# SCH_elliotcard_2024-12-29.net
KiCad netlist of a schematic drawn in EasyEDA
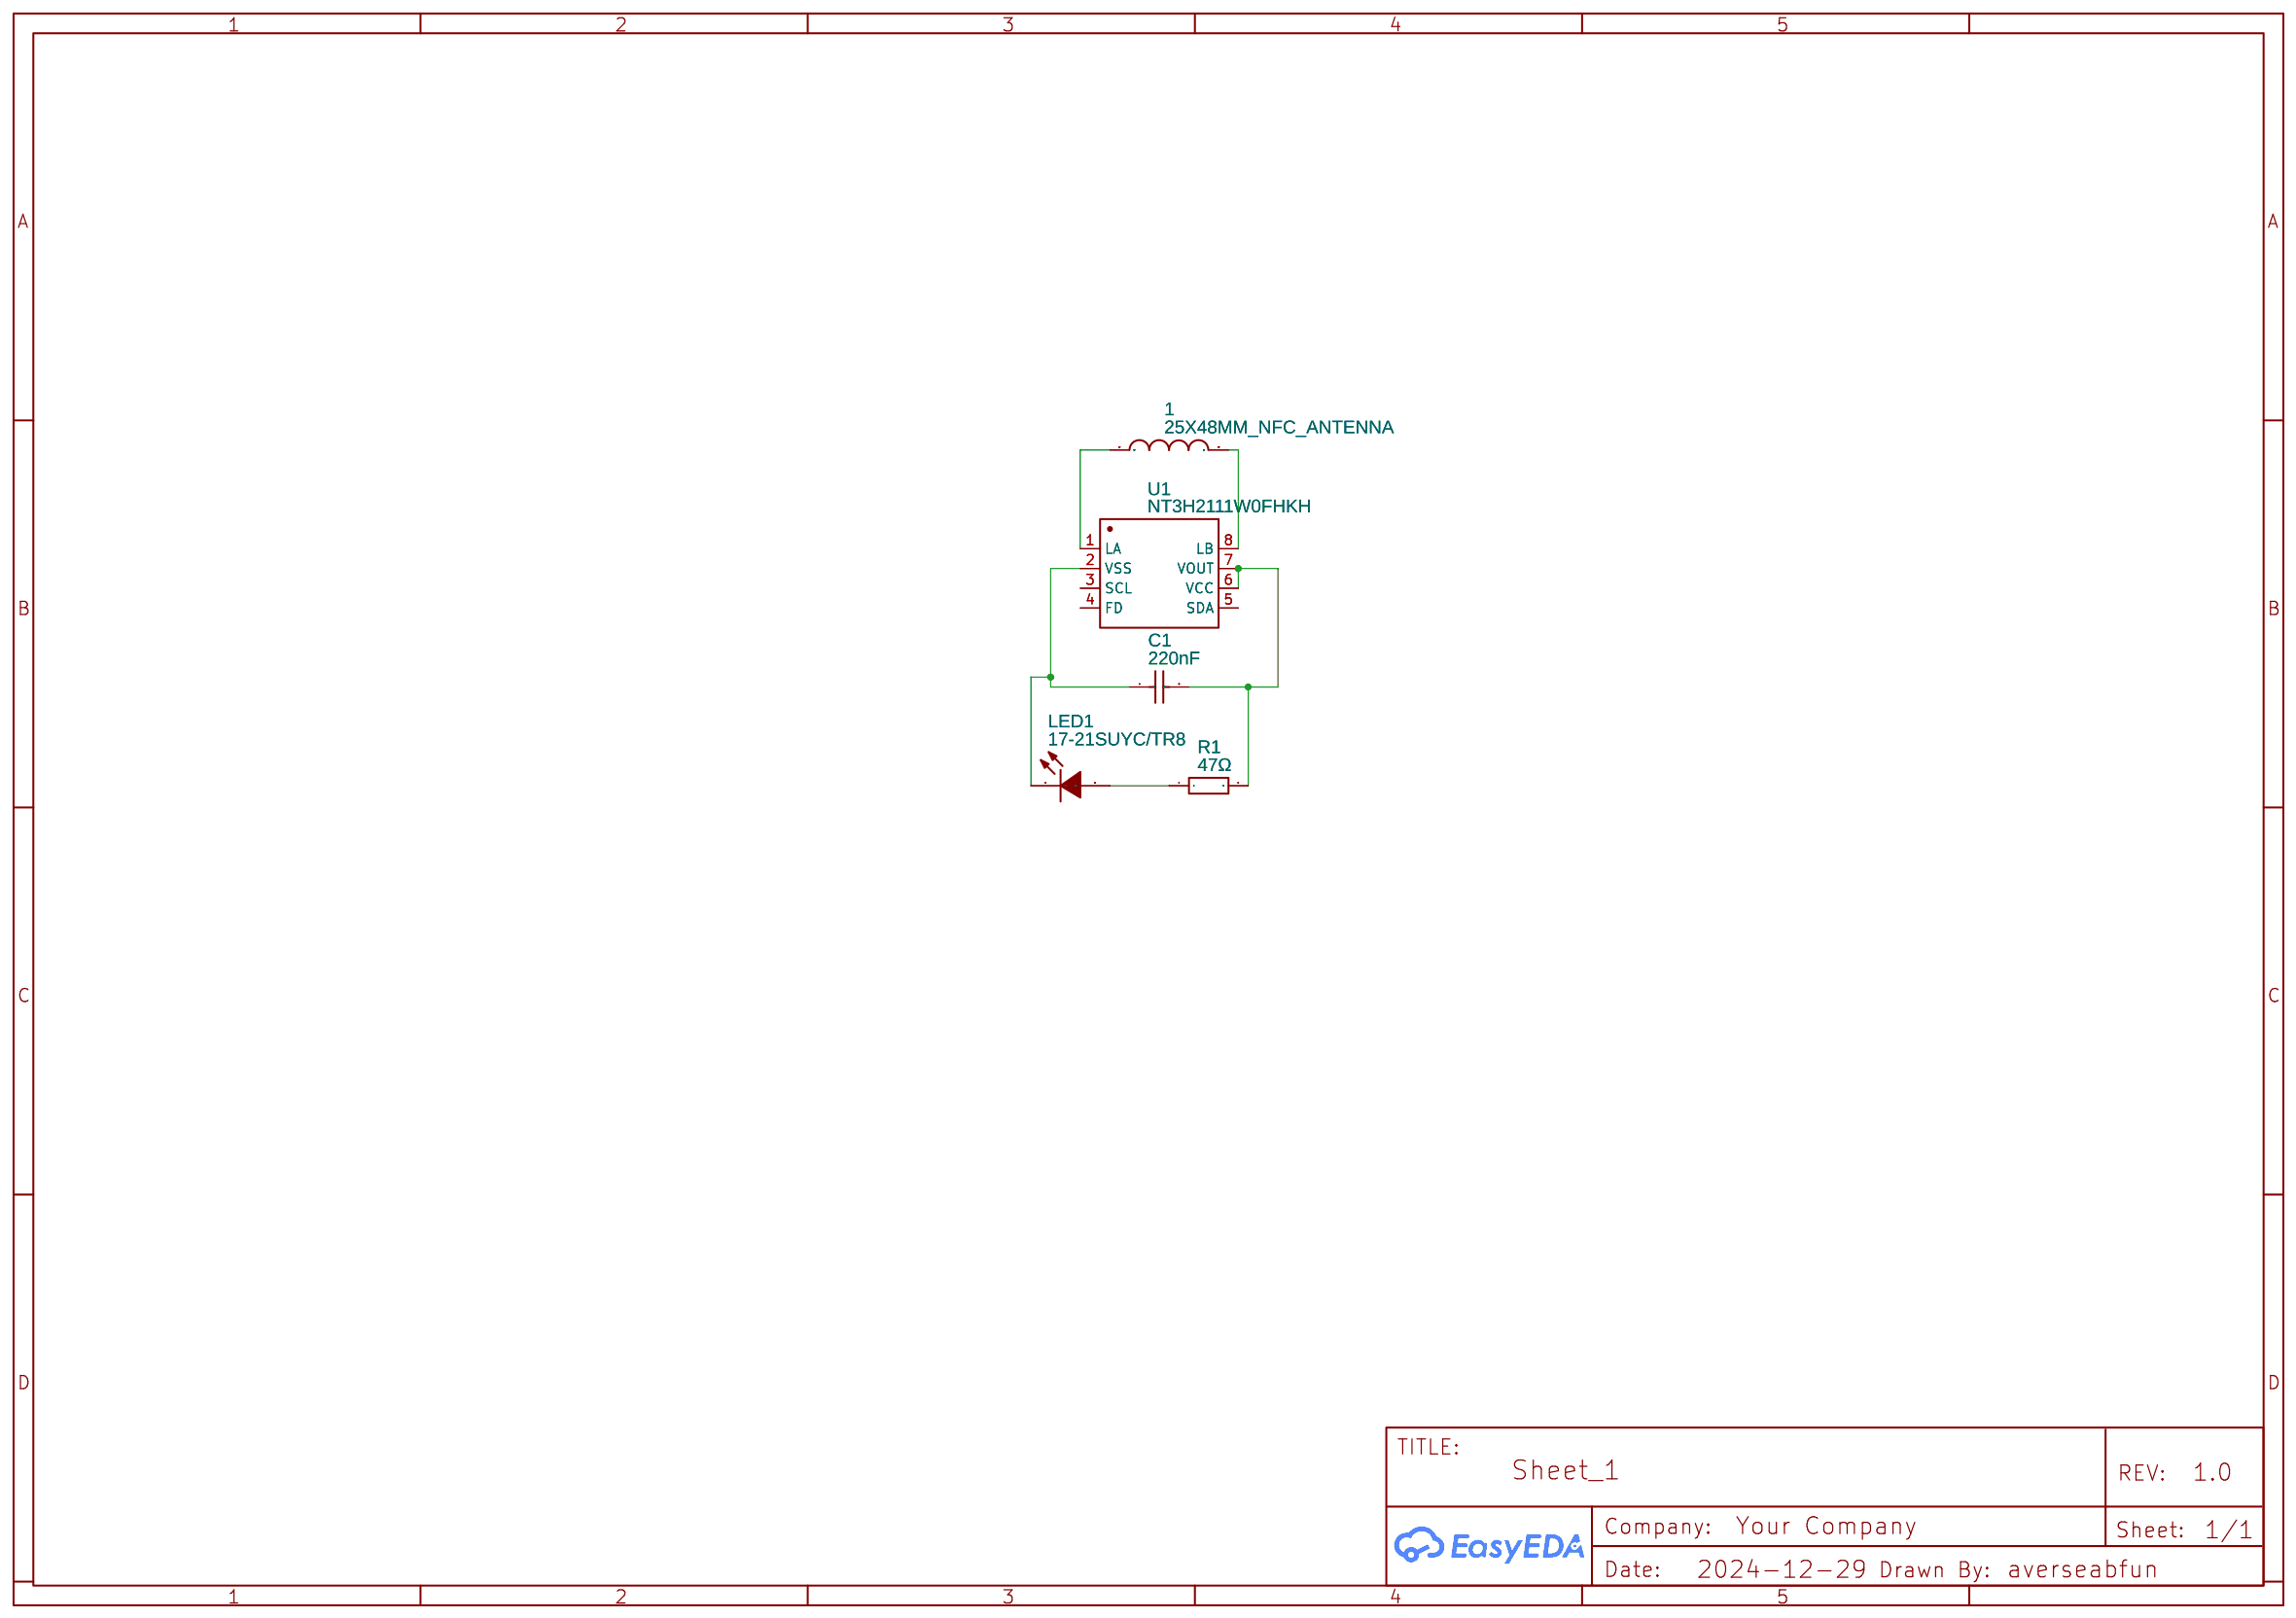
[diagram p0: schematic sheet]

(export (version "E")
  (design (tool "Eeschema 10.0.6"))
  (components
    (comp (ref "1") (value "25X48MM_NFC_ANTENNA") (libsource (lib "") (part "25X48MM_NFC_ANTENNA")))
    (comp (ref "C1")
      (value "220nF")
      (fields
        (field (name "Manufacturer Part") "CL10B224KA8NNNC")
        (field (name "Manufacturer") "SAMSUNG(三星)")
      )
      (libsource (lib "") (part "CL10B224KA8NNNC"))
    )
    (comp (ref "LED1")
      (value "17-21SUYC/TR8")
      (fields (field (name "Manufacturer Part") "KT-0805黄灯") (field (name "Manufacturer") "KENTO"))
      (libsource (lib "") (part "17-21SUYC/TR8"))
    )
    (comp (ref "R1")
      (value "47Ω")
      (fields
        (field (name "Manufacturer Part") "0603WAF470JT5E")
        (field (name "Manufacturer") "UNI-ROYAL(厚声)")
      )
      (libsource (lib "") (part "0603WAF470JT5E"))
    )
    (comp (ref "U1")
      (value "NT3H2111W0FHKH")
      (fields (field (name "Manufacturer") "NXP(恩智浦)"))
      (libsource (lib "") (part "NT3H2111W0FHKH"))
    )
  )
  (nets
    (net (code "1") (name "Net-(LED1-+)") (class "Default")
      (node (ref "LED1") (pin "1") (pinfunction "+_1") (pintype "unspecified"))
      (node (ref "R1") (pin "1") (pinfunction "1_1") (pintype "input"))
    )
    (net (code "2") (name "Net-(LED1--)") (class "Default")
      (node (ref "C1") (pin "1") (pinfunction "1_1") (pintype "input"))
      (node (ref "LED1") (pin "2") (pinfunction "-_2") (pintype "unspecified"))
      (node (ref "U1") (pin "2") (pinfunction "VSS_2") (pintype "unspecified"))
    )
    (net (code "3") (name "Net-(U1-LA)") (class "Default")
      (node (ref "1") (pin "P$1") (pinfunction "P$1_P$1") (pintype "bidirectional"))
      (node (ref "U1") (pin "1") (pinfunction "LA_1") (pintype "unspecified"))
    )
    (net (code "4") (name "Net-(U1-LB)") (class "Default")
      (node (ref "1") (pin "P$2") (pinfunction "P$2_P$2") (pintype "bidirectional"))
      (node (ref "U1") (pin "8") (pinfunction "LB_8") (pintype "unspecified"))
    )
    (net (code "5") (name "Net-(U1-VCC)") (class "Default")
      (node (ref "C1") (pin "2") (pinfunction "2_2") (pintype "input"))
      (node (ref "R1") (pin "2") (pinfunction "2_2") (pintype "input"))
      (node (ref "U1") (pin "6") (pinfunction "VCC_6") (pintype "unspecified"))
      (node (ref "U1") (pin "7") (pinfunction "VOUT_7") (pintype "unspecified"))
    )
    (net (code "6") (name "unconnected-(U1-FD-Pad4)") (class "Default")
      (node (ref "U1") (pin "4") (pinfunction "FD_4") (pintype "unspecified"))
    )
    (net (code "7") (name "unconnected-(U1-SCL-Pad3)") (class "Default")
      (node (ref "U1") (pin "3") (pinfunction "SCL_3") (pintype "unspecified"))
    )
    (net (code "8") (name "unconnected-(U1-SDA-Pad5)") (class "Default")
      (node (ref "U1") (pin "5") (pinfunction "SDA_5") (pintype "unspecified"))
    )
  )
)
